# isolator.net
KiCad netlist of a schematic drawn in EAGLE
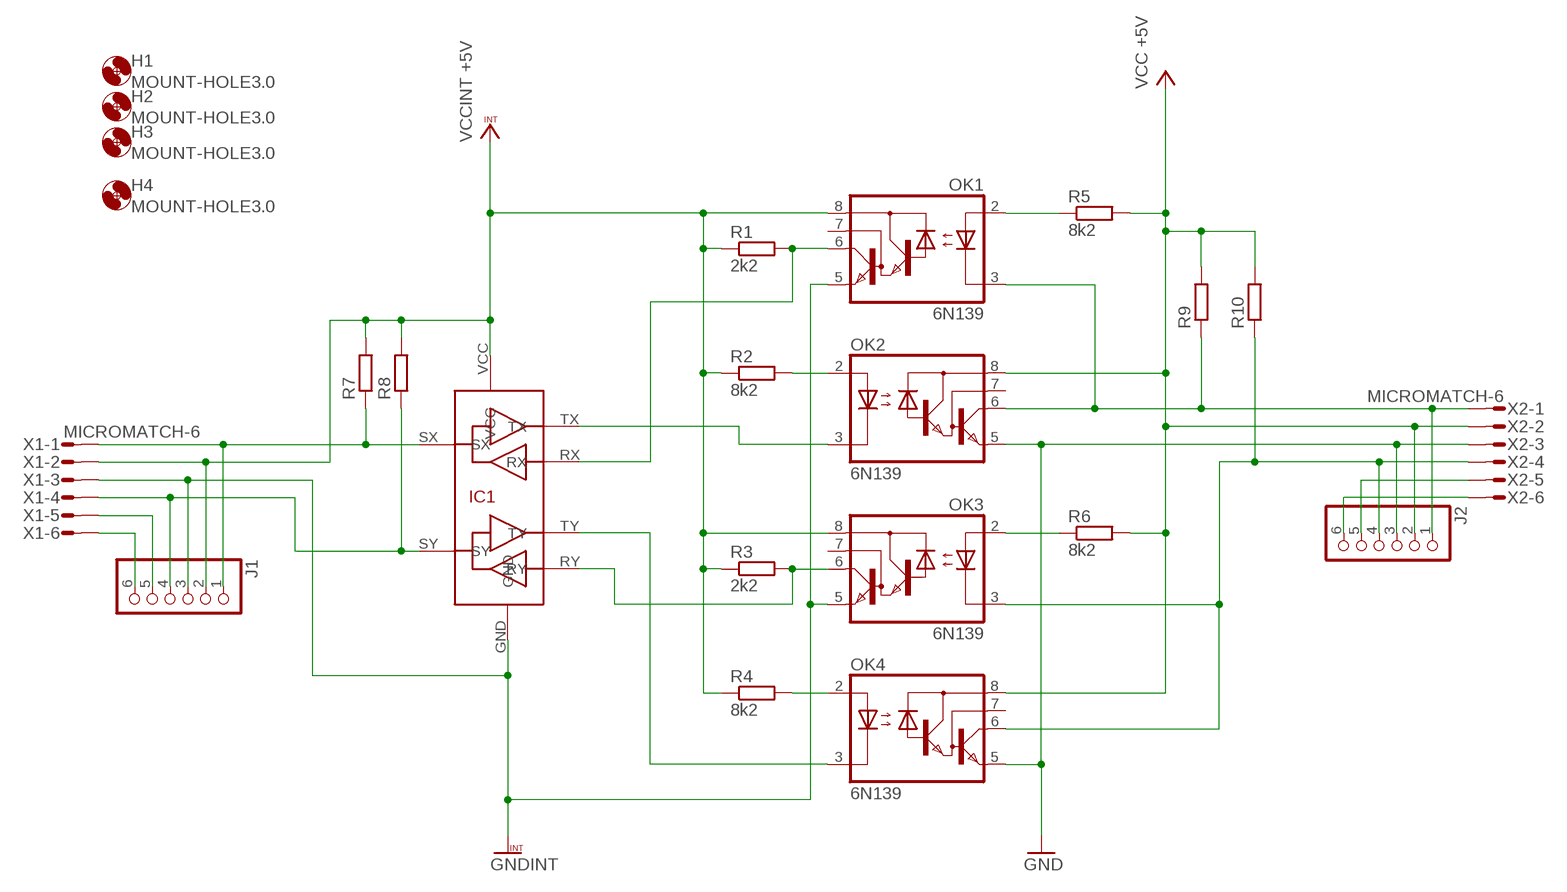
[diagram p0: schematic, sheet 1]

(export (version "E")
  (design (tool "Eeschema 10.0.6"))
  (components
    (comp (ref "H1")
      (value "MOUNT-HOLE3.0")
      (footprint "eagle-import:3,0")
      (libsource (lib "eagle-import") (part "MOUNT-HOLE3.0"))
    )
    (comp (ref "H2")
      (value "MOUNT-HOLE3.0")
      (footprint "eagle-import:3,0")
      (libsource (lib "eagle-import") (part "MOUNT-HOLE3.0"))
    )
    (comp (ref "H3")
      (value "MOUNT-HOLE3.0")
      (footprint "eagle-import:3,0")
      (libsource (lib "eagle-import") (part "MOUNT-HOLE3.0"))
    )
    (comp (ref "H4")
      (value "MOUNT-HOLE3.0")
      (footprint "eagle-import:3,0")
      (libsource (lib "eagle-import") (part "MOUNT-HOLE3.0"))
    )
    (comp (ref "IC1")
      (value "P82B96")
      (footprint "eagle-import:DIL08")
      (libsource (lib "eagle-import") (part "P82B96"))
    )
    (comp (ref "J1")
      (value "PINHD-1X6")
      (footprint "eagle-import:1X06")
      (libsource (lib "eagle-import") (part "PINHD-1X6"))
    )
    (comp (ref "J2")
      (value "PINHD-1X6")
      (footprint "eagle-import:1X06")
      (libsource (lib "eagle-import") (part "PINHD-1X6"))
    )
    (comp (ref "OK1")
      (value "6N139")
      (footprint "eagle-import:DIL08")
      (fields (field (name "MF") "VISHAY/TELEFUNKEN") (field (name "MPN") "6N138"))
      (libsource (lib "eagle-import") (part "6N139"))
    )
    (comp (ref "OK2")
      (value "6N139")
      (footprint "eagle-import:DIL08")
      (fields (field (name "MF") "VISHAY/TELEFUNKEN") (field (name "MPN") "6N138"))
      (libsource (lib "eagle-import") (part "6N139"))
    )
    (comp (ref "OK3")
      (value "6N139")
      (footprint "eagle-import:DIL08")
      (fields (field (name "MF") "VISHAY/TELEFUNKEN") (field (name "MPN") "6N138"))
      (libsource (lib "eagle-import") (part "6N139"))
    )
    (comp (ref "OK4")
      (value "6N139")
      (footprint "eagle-import:DIL08")
      (fields (field (name "MF") "VISHAY/TELEFUNKEN") (field (name "MPN") "6N138"))
      (libsource (lib "eagle-import") (part "6N139"))
    )
    (comp (ref "R1")
      (value "2k2")
      (footprint "eagle-import:0207_10")
      (libsource (lib "eagle-import") (part "R-EU_0207/10"))
    )
    (comp (ref "R2")
      (value "8k2")
      (footprint "eagle-import:0207_10")
      (libsource (lib "eagle-import") (part "R-EU_0207/10"))
    )
    (comp (ref "R3")
      (value "2k2")
      (footprint "eagle-import:0207_10")
      (libsource (lib "eagle-import") (part "R-EU_0207/10"))
    )
    (comp (ref "R4")
      (value "8k2")
      (footprint "eagle-import:0207_10")
      (libsource (lib "eagle-import") (part "R-EU_0207/10"))
    )
    (comp (ref "R5")
      (value "8k2")
      (footprint "eagle-import:0207_10")
      (libsource (lib "eagle-import") (part "R-EU_0207/10"))
    )
    (comp (ref "R6")
      (value "8k2")
      (footprint "eagle-import:0207_10")
      (libsource (lib "eagle-import") (part "R-EU_0207/10"))
    )
    (comp (ref "R7")
      (value "R-EU_0207/10")
      (footprint "eagle-import:0207_10")
      (libsource (lib "eagle-import") (part "R-EU_0207/10"))
    )
    (comp (ref "R8")
      (value "R-EU_0207/10")
      (footprint "eagle-import:0207_10")
      (libsource (lib "eagle-import") (part "R-EU_0207/10"))
    )
    (comp (ref "R9")
      (value "R-EU_0207/10")
      (footprint "eagle-import:0207_10")
      (libsource (lib "eagle-import") (part "R-EU_0207/10"))
    )
    (comp (ref "R10")
      (value "R-EU_0207/10")
      (footprint "eagle-import:0207_10")
      (libsource (lib "eagle-import") (part "R-EU_0207/10"))
    )
    (comp (ref "X1")
      (value "MICROMATCH-6")
      (footprint "eagle-import:MICROMATCH-6")
      (fields (field (name "MPN") "7-215464-6"))
      (libsource (lib "eagle-import") (part "MICROMATCH-6"))
    )
    (comp (ref "X2")
      (value "MICROMATCH-6")
      (footprint "eagle-import:MICROMATCH-6")
      (fields (field (name "MPN") "7-215464-6"))
      (libsource (lib "eagle-import") (part "MICROMATCH-6"))
    )
  )
  (nets
    (net (code "1") (name "GND") (class "Default")
      (node (ref "J2") (pin "3") (pinfunction "3_3") (pintype "passive"))
      (node (ref "OK2") (pin "5") (pinfunction "GND_5") (pintype "passive"))
      (node (ref "OK4") (pin "5") (pinfunction "GND_5") (pintype "passive"))
      (node (ref "X2") (pin "3") (pinfunction "S_3") (pintype "passive"))
    )
    (net (code "2") (name "GNDINT") (class "Default")
      (node (ref "IC1") (pin "GND") (pinfunction "GND_GND") (pintype "bidirectional"))
      (node (ref "J1") (pin "3") (pinfunction "3_3") (pintype "passive"))
      (node (ref "OK1") (pin "5") (pinfunction "GND_5") (pintype "passive"))
      (node (ref "OK3") (pin "5") (pinfunction "GND_5") (pintype "passive"))
      (node (ref "X1") (pin "3") (pinfunction "S_3") (pintype "passive"))
    )
    (net (code "3") (name "Net-(OK1-A)") (class "Default")
      (node (ref "OK1") (pin "2") (pinfunction "A_2") (pintype "passive"))
      (node (ref "R5") (pin "1") (pinfunction "1_1") (pintype "passive"))
    )
    (net (code "4") (name "Net-(OK1-C)") (class "Default")
      (node (ref "J2") (pin "1") (pinfunction "1_1") (pintype "passive"))
      (node (ref "OK1") (pin "3") (pinfunction "C_3") (pintype "passive"))
      (node (ref "OK2") (pin "6") (pinfunction "VO_6") (pintype "passive"))
      (node (ref "R9") (pin "1") (pinfunction "1_1") (pintype "passive"))
      (node (ref "X2") (pin "1") (pinfunction "S_1") (pintype "passive"))
    )
    (net (code "5") (name "Net-(OK1-VO)") (class "Default")
      (node (ref "IC1") (pin "RX") (pinfunction "RX_RX") (pintype "bidirectional"))
      (node (ref "OK1") (pin "6") (pinfunction "VO_6") (pintype "passive"))
      (node (ref "R1") (pin "2") (pinfunction "2_2") (pintype "passive"))
    )
    (net (code "6") (name "Net-(OK2-A)") (class "Default")
      (node (ref "OK2") (pin "2") (pinfunction "A_2") (pintype "passive"))
      (node (ref "R2") (pin "2") (pinfunction "2_2") (pintype "passive"))
    )
    (net (code "7") (name "Net-(OK2-C)") (class "Default")
      (node (ref "IC1") (pin "TX") (pinfunction "TX_TX") (pintype "bidirectional"))
      (node (ref "OK2") (pin "3") (pinfunction "C_3") (pintype "passive"))
    )
    (net (code "8") (name "Net-(OK3-A)") (class "Default")
      (node (ref "OK3") (pin "2") (pinfunction "A_2") (pintype "passive"))
      (node (ref "R6") (pin "1") (pinfunction "1_1") (pintype "passive"))
    )
    (net (code "9") (name "Net-(OK3-C)") (class "Default")
      (node (ref "J2") (pin "4") (pinfunction "4_4") (pintype "passive"))
      (node (ref "OK3") (pin "3") (pinfunction "C_3") (pintype "passive"))
      (node (ref "OK4") (pin "6") (pinfunction "VO_6") (pintype "passive"))
      (node (ref "R10") (pin "1") (pinfunction "1_1") (pintype "passive"))
      (node (ref "X2") (pin "4") (pinfunction "S_4") (pintype "passive"))
    )
    (net (code "10") (name "Net-(OK3-VO)") (class "Default")
      (node (ref "IC1") (pin "RY") (pinfunction "RY_RY") (pintype "bidirectional"))
      (node (ref "OK3") (pin "6") (pinfunction "VO_6") (pintype "passive"))
      (node (ref "R3") (pin "2") (pinfunction "2_2") (pintype "passive"))
    )
    (net (code "11") (name "Net-(OK4-A)") (class "Default")
      (node (ref "OK4") (pin "2") (pinfunction "A_2") (pintype "passive"))
      (node (ref "R4") (pin "2") (pinfunction "2_2") (pintype "passive"))
    )
    (net (code "12") (name "Net-(OK4-C)") (class "Default")
      (node (ref "IC1") (pin "TY") (pinfunction "TY_TY") (pintype "bidirectional"))
      (node (ref "OK4") (pin "3") (pinfunction "C_3") (pintype "passive"))
    )
    (net (code "13") (name "Net-(X1A-S)") (class "Default")
      (node (ref "IC1") (pin "SX") (pinfunction "SX_SX") (pintype "bidirectional"))
      (node (ref "J1") (pin "1") (pinfunction "1_1") (pintype "passive"))
      (node (ref "R7") (pin "1") (pinfunction "1_1") (pintype "passive"))
      (node (ref "X1") (pin "1") (pinfunction "S_1") (pintype "passive"))
    )
    (net (code "14") (name "Net-(X1D-S)") (class "Default")
      (node (ref "IC1") (pin "SY") (pinfunction "SY_SY") (pintype "bidirectional"))
      (node (ref "J1") (pin "4") (pinfunction "4_4") (pintype "passive"))
      (node (ref "R8") (pin "1") (pinfunction "1_1") (pintype "passive"))
      (node (ref "X1") (pin "4") (pinfunction "S_4") (pintype "passive"))
    )
    (net (code "15") (name "Net-(X1E-S)") (class "Default")
      (node (ref "J1") (pin "5") (pinfunction "5_5") (pintype "passive"))
      (node (ref "X1") (pin "5") (pinfunction "S_5") (pintype "passive"))
    )
    (net (code "16") (name "Net-(X1F-S)") (class "Default")
      (node (ref "J1") (pin "6") (pinfunction "6_6") (pintype "passive"))
      (node (ref "X1") (pin "6") (pinfunction "S_6") (pintype "passive"))
    )
    (net (code "17") (name "Net-(X2E-S)") (class "Default")
      (node (ref "J2") (pin "5") (pinfunction "5_5") (pintype "passive"))
      (node (ref "X2") (pin "5") (pinfunction "S_5") (pintype "passive"))
    )
    (net (code "18") (name "Net-(X2F-S)") (class "Default")
      (node (ref "J2") (pin "6") (pinfunction "6_6") (pintype "passive"))
      (node (ref "X2") (pin "6") (pinfunction "S_6") (pintype "passive"))
    )
    (net (code "19") (name "VCC +5V") (class "Default")
      (node (ref "J2") (pin "2") (pinfunction "2_2") (pintype "passive"))
      (node (ref "OK2") (pin "8") (pinfunction "VCC_8") (pintype "passive"))
      (node (ref "OK4") (pin "8") (pinfunction "VCC_8") (pintype "passive"))
      (node (ref "R10") (pin "2") (pinfunction "2_2") (pintype "passive"))
      (node (ref "R5") (pin "2") (pinfunction "2_2") (pintype "passive"))
      (node (ref "R6") (pin "2") (pinfunction "2_2") (pintype "passive"))
      (node (ref "R9") (pin "2") (pinfunction "2_2") (pintype "passive"))
      (node (ref "X2") (pin "2") (pinfunction "S_2") (pintype "passive"))
    )
    (net (code "20") (name "VCCINT +5V") (class "Default")
      (node (ref "IC1") (pin "VCC") (pinfunction "VCC_VCC") (pintype "bidirectional"))
      (node (ref "J1") (pin "2") (pinfunction "2_2") (pintype "passive"))
      (node (ref "OK1") (pin "8") (pinfunction "VCC_8") (pintype "passive"))
      (node (ref "OK3") (pin "8") (pinfunction "VCC_8") (pintype "passive"))
      (node (ref "R1") (pin "1") (pinfunction "1_1") (pintype "passive"))
      (node (ref "R2") (pin "1") (pinfunction "1_1") (pintype "passive"))
      (node (ref "R3") (pin "1") (pinfunction "1_1") (pintype "passive"))
      (node (ref "R4") (pin "1") (pinfunction "1_1") (pintype "passive"))
      (node (ref "R7") (pin "2") (pinfunction "2_2") (pintype "passive"))
      (node (ref "R8") (pin "2") (pinfunction "2_2") (pintype "passive"))
      (node (ref "X1") (pin "2") (pinfunction "S_2") (pintype "passive"))
    )
    (net (code "21") (name "unconnected-(OK1-VB-Pad7)") (class "Default")
      (node (ref "OK1") (pin "7") (pinfunction "VB_7") (pintype "passive"))
    )
    (net (code "22") (name "unconnected-(OK2-VB-Pad7)") (class "Default")
      (node (ref "OK2") (pin "7") (pinfunction "VB_7") (pintype "passive"))
    )
    (net (code "23") (name "unconnected-(OK3-VB-Pad7)") (class "Default")
      (node (ref "OK3") (pin "7") (pinfunction "VB_7") (pintype "passive"))
    )
    (net (code "24") (name "unconnected-(OK4-VB-Pad7)") (class "Default")
      (node (ref "OK4") (pin "7") (pinfunction "VB_7") (pintype "passive"))
    )
  )
)
